# Charger_Main_Power.net
KiCad netlist of a schematic drawn in Altium Designer
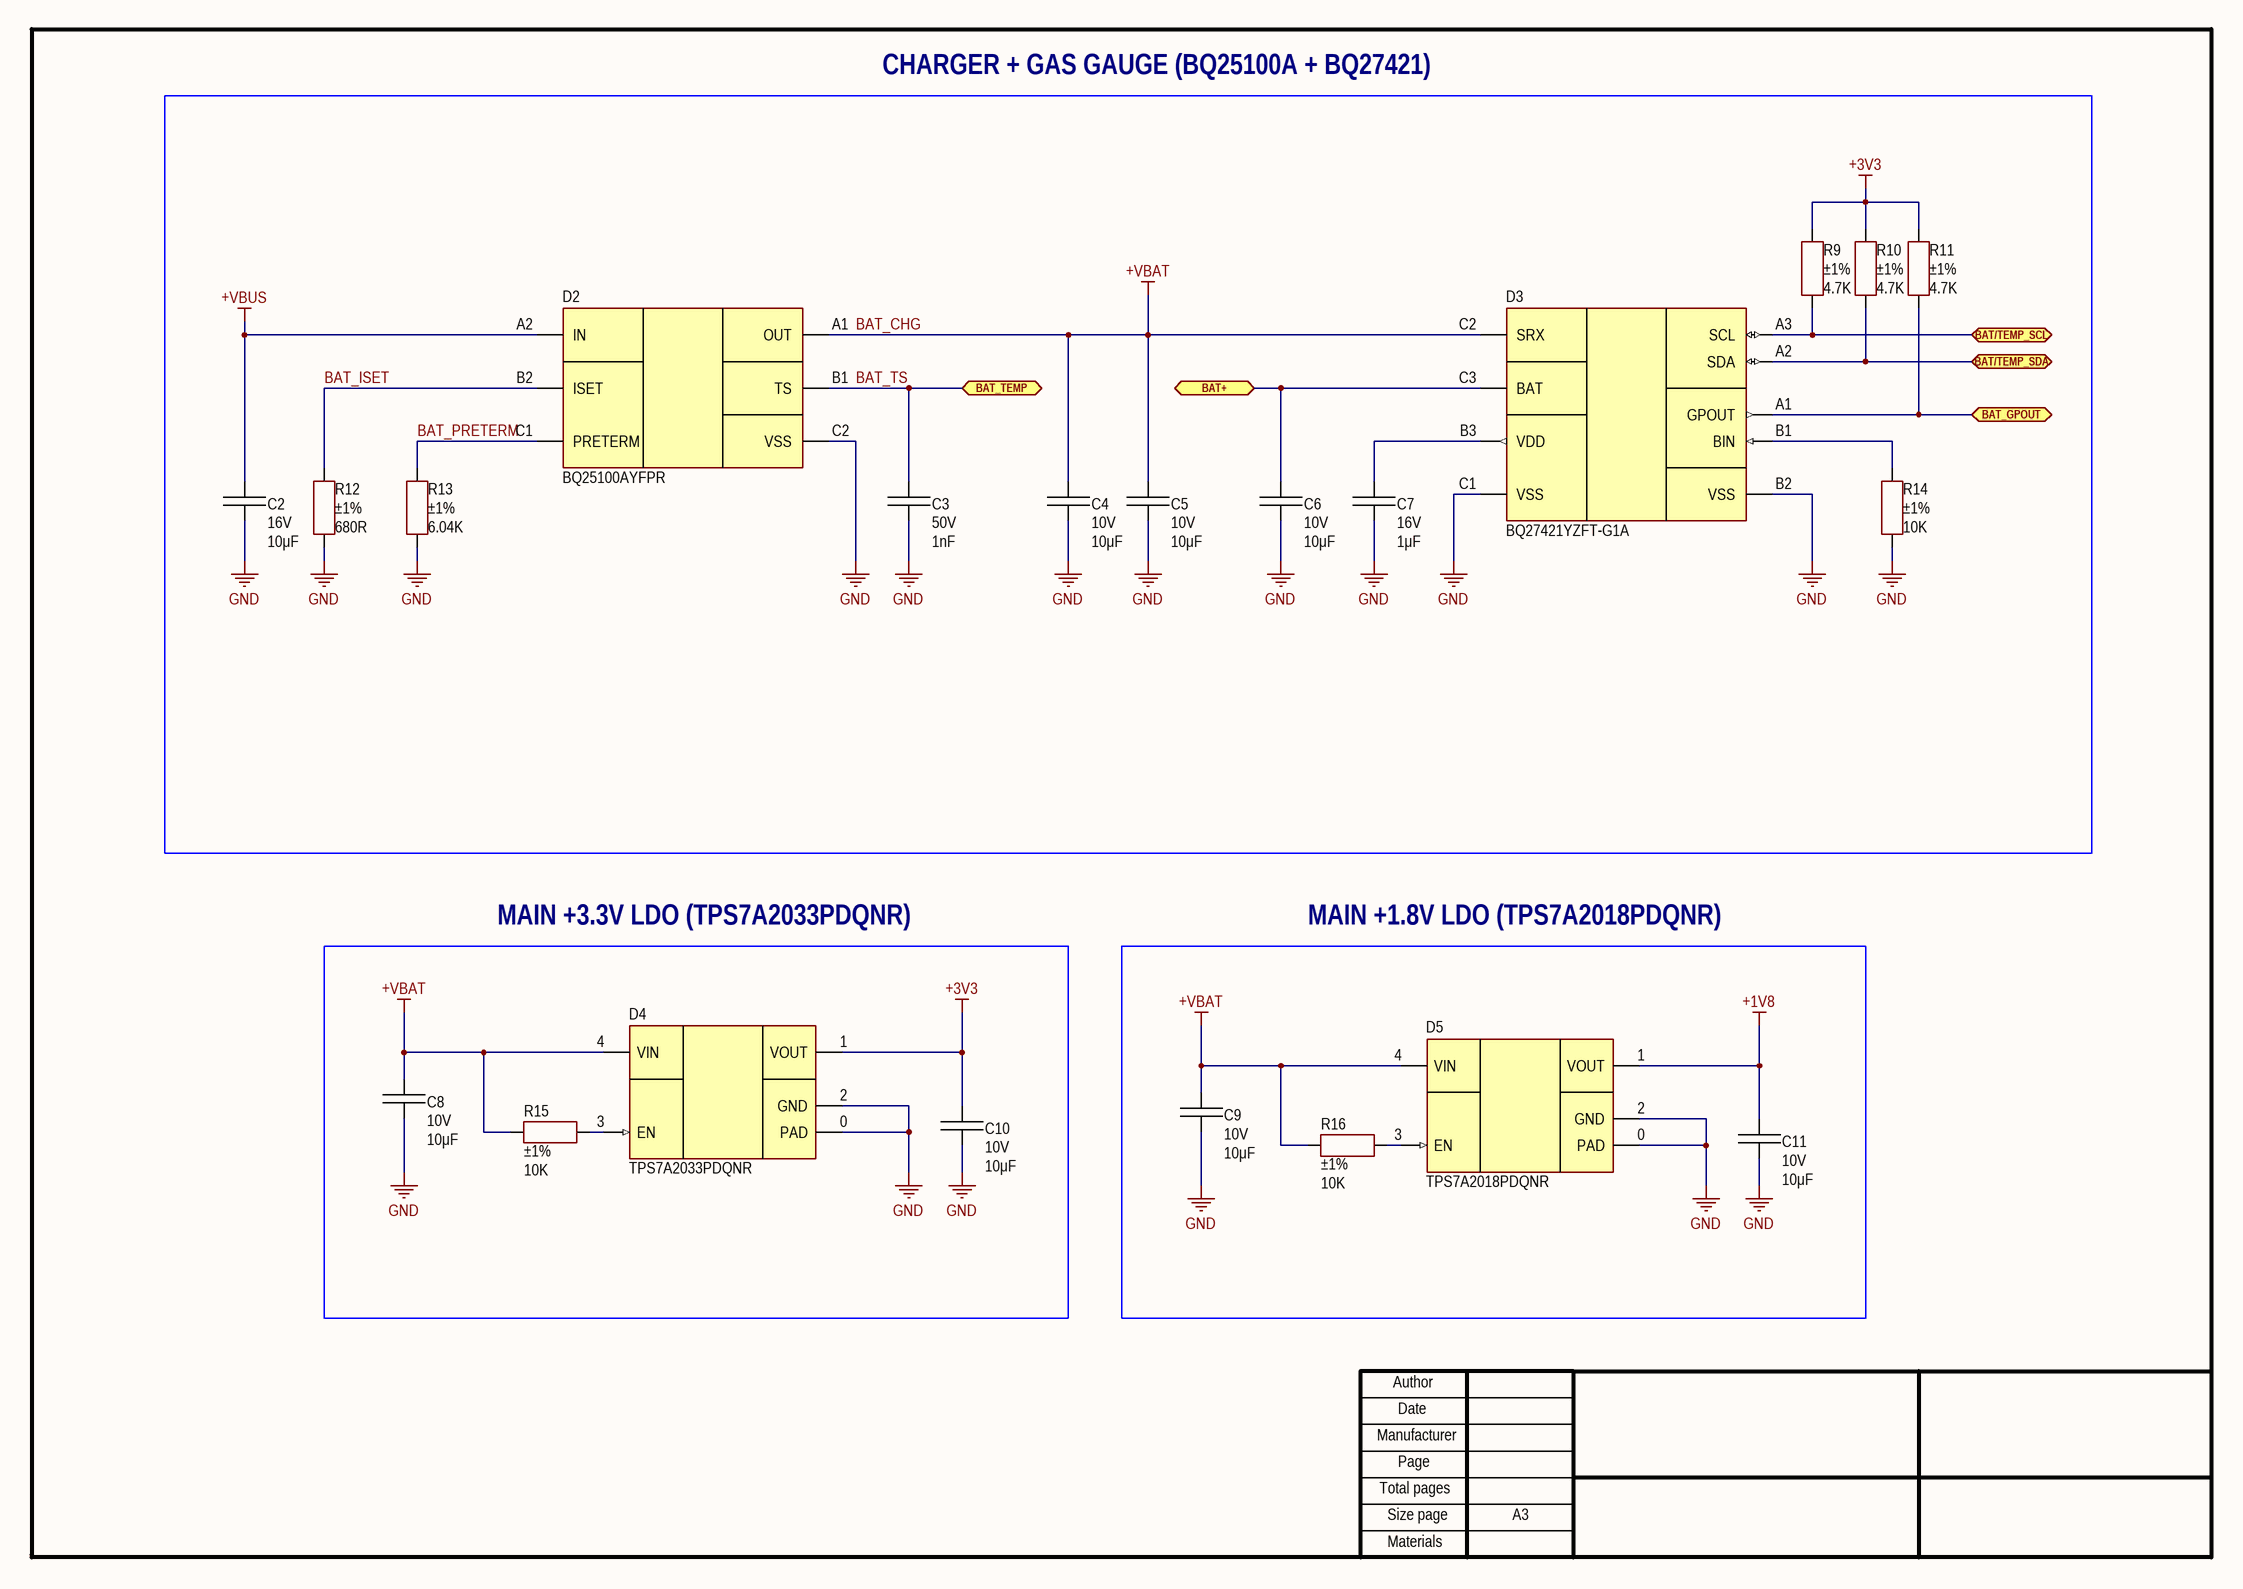
[diagram p0: Charger+Main_Power — копия.SchDoc]

(export (version "E")
  (design (tool "Eeschema 10.0.6"))
  (components
    (comp (ref "C2")
      (value "10μF")
      (footprint "CAP: 0805_NO_SILK")
      (description "10 µF ±20% 16V Ceramic Capacitor X7R 0805 (2012 Metric)")
      (fields
        (field (name "MANUFACTURER") "Yageo")
        (field (name "PARTNUMBER") "CC0805MKX7R7BB106")
        (field (name "VOLTAGE") "16V")
      )
      (libsource (lib "capacitor") (part "Ceramic_0805"))
    )
    (comp (ref "C3")
      (value "1nF")
      (footprint "CAP: 0805")
      (description "1000 pF ±5% 50V Ceramic Capacitor C0G, NP0 0805 (2012 Metric)")
      (fields
        (field (name "MANUFACTURER") "Yageo")
        (field (name "PARTNUMBER") "CC0805JRNPO9BN102")
        (field (name "VOLTAGE") "50V")
      )
      (libsource (lib "capacitor") (part "Ceramic_0805"))
    )
    (comp (ref "C4")
      (value "10μF")
      (footprint "CAP: 0805")
      (description "10 µF ±10% 10V Ceramic Capacitor X7R 0805 (2012 Metric)")
      (fields
        (field (name "MANUFACTURER") "Yageo")
        (field (name "PARTNUMBER") "CC0805KFX7R6BB106")
        (field (name "VOLTAGE") "10V")
      )
      (libsource (lib "capacitor") (part "Ceramic_0805"))
    )
    (comp (ref "C5")
      (value "10μF")
      (footprint "CAP: 0805")
      (description "10 µF ±10% 10V Ceramic Capacitor X7R 0805 (2012 Metric)")
      (fields
        (field (name "MANUFACTURER") "Yageo")
        (field (name "PARTNUMBER") "CC0805KFX7R6BB106")
        (field (name "VOLTAGE") "10V")
      )
      (libsource (lib "capacitor") (part "Ceramic_0805"))
    )
    (comp (ref "C6")
      (value "10μF")
      (footprint "CAP: 0805")
      (description "10 µF ±10% 10V Ceramic Capacitor X7R 0805 (2012 Metric)")
      (fields
        (field (name "MANUFACTURER") "Yageo")
        (field (name "PARTNUMBER") "CC0805KFX7R6BB106")
        (field (name "VOLTAGE") "10V")
      )
      (libsource (lib "capacitor") (part "Ceramic_0805"))
    )
    (comp (ref "C7")
      (value "1μF")
      (footprint "CAP: 0805")
      (description "1 µF ±10% 16V Ceramic Capacitor X7R 0805 (2012 Metric)")
      (fields
        (field (name "MANUFACTURER") "Yageo")
        (field (name "PARTNUMBER") "CC0805KKX7R7BB105")
        (field (name "VOLTAGE") "16V")
      )
      (libsource (lib "capacitor") (part "Ceramic_0805"))
    )
    (comp (ref "C8")
      (value "10μF")
      (footprint "CAP: 0805")
      (description "10 µF ±10% 10V Ceramic Capacitor X7R 0805 (2012 Metric)")
      (fields
        (field (name "MANUFACTURER") "Yageo")
        (field (name "PARTNUMBER") "CC0805KFX7R6BB106")
        (field (name "VOLTAGE") "10V")
      )
      (libsource (lib "capacitor") (part "Ceramic_0805"))
    )
    (comp (ref "C9")
      (value "10μF")
      (footprint "CAP: 0805")
      (description "10 µF ±10% 10V Ceramic Capacitor X7R 0805 (2012 Metric)")
      (fields
        (field (name "MANUFACTURER") "Yageo")
        (field (name "PARTNUMBER") "CC0805KFX7R6BB106")
        (field (name "VOLTAGE") "10V")
      )
      (libsource (lib "capacitor") (part "Ceramic_0805"))
    )
    (comp (ref "C10")
      (value "10μF")
      (footprint "CAP: 0805")
      (description "10 µF ±10% 10V Ceramic Capacitor X7R 0805 (2012 Metric)")
      (fields
        (field (name "MANUFACTURER") "Yageo")
        (field (name "PARTNUMBER") "CC0805KFX7R6BB106")
        (field (name "VOLTAGE") "10V")
      )
      (libsource (lib "capacitor") (part "Ceramic_0805"))
    )
    (comp (ref "C11")
      (value "10μF")
      (footprint "CAP: 0805")
      (description "10 µF ±10% 10V Ceramic Capacitor X7R 0805 (2012 Metric)")
      (fields
        (field (name "MANUFACTURER") "Yageo")
        (field (name "PARTNUMBER") "CC0805KFX7R6BB106")
        (field (name "VOLTAGE") "10V")
      )
      (libsource (lib "capacitor") (part "Ceramic_0805"))
    )
    (comp (ref "D2")
      (value "~")
      (footprint "IC: BQ25100")
      (description "PMIC")
      (fields
        (field (name "MANUFACTURER") "Texas Instruments")
        (field (name "VALUEMANUFACTURERPARTNUMBER") "PMIC, Li-Ion/Li-Po, 4.45...6.45V, -40...+85°C, 10-WSON")
        (field (name "PARTNUMBER") "BQ25100AYFPR")
      )
      (libsource (lib "MyLib") (part "BQ25100AYFPR"))
    )
    (comp (ref "D3")
      (value "~")
      (footprint "IC: 9-DSBGA")
      (description "Gas gauge")
      (fields
        (field (name "MANUFACTURER") "Texas Instruments")
        (field (name "VALUEMANUFACTURERPARTNUMBER") "Gas gauge, Li-Ion, 2.45...4.5V, -40...+85°C, 9-DSBGA")
        (field (name "PARTNUMBER") "BQ27421YZFT-G1A")
      )
      (libsource (lib "MyLib") (part "BQ25100AYFPR_1"))
    )
    (comp (ref "D4")
      (value "~")
      (footprint "IC: 4-X2SON")
      (description "Linear voltage regulator")
      (fields
        (field (name "MANUFACTURER") "Texas Instruments")
        (field (name "VALUEMANUFACTURERPARTNUMBER") "Linear voltage regulator, input 3.44...6V, 2V, 3.3V, 0.3A, -40...+125°C, 4-X2SON")
        (field (name "PARTNUMBER") "TPS7A2033PDQNR")
      )
      (libsource (lib "MyLib") (part "TPS7A2033"))
    )
    (comp (ref "D5")
      (value "~")
      (footprint "IC: 4-X2SON")
      (description "Linear voltage regulator")
      (fields
        (field (name "MANUFACTURER") "Texas Instruments")
        (field (name "VALUEMANUFACTURERPARTNUMBER") "Linear voltage regulator, input 2...6V, 2V, 1.8V, 0.3A, -40...+125°C, 4-X2SON")
        (field (name "PARTNUMBER") "TPS7A2018PDQNR")
      )
      (libsource (lib "MyLib") (part "TPS7A2033"))
    )
    (comp (ref "R9")
      (value "4.7K")
      (footprint "RES: 0805")
      (description "4.7 kOhms ±5% 0.125W, 1/8W Chip Resistor 0805 (2012 Metric) Moisture Resistant Thick Film")
      (fields
        (field (name "MANUFACTURER") "Yageo")
        (field (name "PARTNUMBER") "RC0805JR-074K7L")
        (field (name "TOLERANCE") "±1%")
      )
      (libsource (lib "resistor") (part "Resistor_0805"))
    )
    (comp (ref "R10")
      (value "4.7K")
      (footprint "RES: 0805")
      (description "4.7 kOhms ±5% 0.125W, 1/8W Chip Resistor 0805 (2012 Metric) Moisture Resistant Thick Film")
      (fields
        (field (name "MANUFACTURER") "Yageo")
        (field (name "PARTNUMBER") "RC0805JR-074K7L")
        (field (name "TOLERANCE") "±1%")
      )
      (libsource (lib "resistor") (part "Resistor_0805"))
    )
    (comp (ref "R11")
      (value "4.7K")
      (footprint "RES: 0805")
      (description "4.7 kOhms ±5% 0.125W, 1/8W Chip Resistor 0805 (2012 Metric) Moisture Resistant Thick Film")
      (fields
        (field (name "MANUFACTURER") "Yageo")
        (field (name "PARTNUMBER") "RC0805JR-074K7L")
        (field (name "TOLERANCE") "±1%")
      )
      (libsource (lib "resistor") (part "Resistor_0805"))
    )
    (comp (ref "R12")
      (value "680R")
      (footprint "RES: 0805")
      (description "680 Ohms ±1% 0.125W, 1/8W Chip Resistor 0805 (2012 Metric) Moisture Resistant Thick Film")
      (fields
        (field (name "MANUFACTURER") "Yageo")
        (field (name "PARTNUMBER") "RC0805FR-07680RL")
        (field (name "TOLERANCE") "±1%")
      )
      (libsource (lib "resistor") (part "Resistor_0805"))
    )
    (comp (ref "R13")
      (value "6.04K")
      (footprint "RES: 0805")
      (description "6.04 kOhms ±1% 0.125W, 1/8W Chip Resistor 0805 (2012 Metric) Moisture Resistant Thick Film")
      (fields
        (field (name "MANUFACTURER") "Yageo")
        (field (name "PARTNUMBER") "RC0805FR-076K04L")
        (field (name "TOLERANCE") "±1%")
      )
      (libsource (lib "resistor") (part "Resistor_0805"))
    )
    (comp (ref "R14")
      (value "10K")
      (footprint "RES: 0805")
      (description "10 kOhms ±1% 0.125W, 1/8W Chip Resistor 0805 (2012 Metric) Moisture Resistant Thick Film")
      (fields
        (field (name "MANUFACTURER") "Yageo")
        (field (name "PARTNUMBER") "RC0805FR-0710KL")
        (field (name "TOLERANCE") "±1%")
      )
      (libsource (lib "resistor") (part "Resistor_0805"))
    )
    (comp (ref "R15")
      (value "10K")
      (footprint "RES: 0805")
      (description "10 kOhms ±1% 0.125W, 1/8W Chip Resistor 0805 (2012 Metric) Moisture Resistant Thick Film")
      (fields
        (field (name "MANUFACTURER") "Yageo")
        (field (name "PARTNUMBER") "RC0805FR-0710KL")
        (field (name "TOLERANCE") "±1%")
      )
      (libsource (lib "") (part "Resistor_0805_1"))
    )
    (comp (ref "R16")
      (value "10K")
      (footprint "RES: 0805")
      (description "10 kOhms ±1% 0.125W, 1/8W Chip Resistor 0805 (2012 Metric) Moisture Resistant Thick Film")
      (fields
        (field (name "MANUFACTURER") "Yageo")
        (field (name "PARTNUMBER") "RC0805FR-0710KL")
        (field (name "TOLERANCE") "±1%")
      )
      (libsource (lib "") (part "Resistor_0805_1"))
    )
  )
  (nets
    (net (code "1") (name "+1V8") (class "Default")
      (node (ref "C11") (pin "2") (pinfunction "2_2") (pintype "passive"))
      (node (ref "D5") (pin "1") (pinfunction "VOUT_1") (pintype "power_in"))
    )
    (net (code "2") (name "+3V3") (class "Default")
      (node (ref "C10") (pin "2") (pinfunction "2_2") (pintype "passive"))
      (node (ref "D4") (pin "1") (pinfunction "VOUT_1") (pintype "power_in"))
      (node (ref "R10") (pin "1") (pinfunction "1_1") (pintype "passive"))
      (node (ref "R11") (pin "1") (pinfunction "1_1") (pintype "passive"))
      (node (ref "R9") (pin "1") (pinfunction "1_1") (pintype "passive"))
    )
    (net (code "3") (name "+VBAT") (class "Default")
      (node (ref "C4") (pin "2") (pinfunction "2_2") (pintype "passive"))
      (node (ref "C5") (pin "2") (pinfunction "2_2") (pintype "passive"))
      (node (ref "C8") (pin "2") (pinfunction "2_2") (pintype "passive"))
      (node (ref "C9") (pin "2") (pinfunction "2_2") (pintype "passive"))
      (node (ref "D2") (pin "A1") (pinfunction "OUT_A1") (pintype "passive"))
      (node (ref "D3") (pin "C2") (pinfunction "SRX_C2") (pintype "power_in"))
      (node (ref "D4") (pin "4") (pinfunction "VIN_4") (pintype "power_in"))
      (node (ref "D5") (pin "4") (pinfunction "VIN_4") (pintype "power_in"))
      (node (ref "R15") (pin "2") (pinfunction "2_2") (pintype "passive"))
      (node (ref "R16") (pin "2") (pinfunction "2_2") (pintype "passive"))
    )
    (net (code "4") (name "+VBUS") (class "Default")
      (node (ref "C2") (pin "2") (pinfunction "2_2") (pintype "passive"))
      (node (ref "D2") (pin "A2") (pinfunction "IN_A2") (pintype "passive"))
    )
    (net (code "5") (name "/BAT+") (class "Default")
      (node (ref "C6") (pin "2") (pinfunction "2_2") (pintype "passive"))
      (node (ref "D3") (pin "C3") (pinfunction "BAT_C3") (pintype "power_in"))
    )
    (net (code "6") (name "/BAT_GPOUT") (class "Default")
      (node (ref "D3") (pin "A1") (pinfunction "GPOUT_A1") (pintype "output"))
      (node (ref "R11") (pin "2") (pinfunction "2_2") (pintype "passive"))
    )
    (net (code "7") (name "/BAT_ISET") (class "Default")
      (node (ref "D2") (pin "B2") (pinfunction "ISET_B2") (pintype "passive"))
      (node (ref "R12") (pin "1") (pinfunction "1_1") (pintype "passive"))
    )
    (net (code "8") (name "/BAT_PRETERM") (class "Default")
      (node (ref "D2") (pin "C1") (pinfunction "PRETERM_C1") (pintype "passive"))
      (node (ref "R13") (pin "1") (pinfunction "1_1") (pintype "passive"))
    )
    (net (code "9") (name "/BAT_TS") (class "Default")
      (node (ref "C3") (pin "2") (pinfunction "2_2") (pintype "passive"))
      (node (ref "D2") (pin "B1") (pinfunction "TS_B1") (pintype "passive"))
    )
    (net (code "10") (name "/BAT{slash}TEMP_SCL") (class "Default")
      (node (ref "D3") (pin "A3") (pinfunction "SCL_A3") (pintype "bidirectional"))
      (node (ref "R9") (pin "2") (pinfunction "2_2") (pintype "passive"))
    )
    (net (code "11") (name "/BAT{slash}TEMP_SDA") (class "Default")
      (node (ref "D3") (pin "A2") (pinfunction "SDA_A2") (pintype "bidirectional"))
      (node (ref "R10") (pin "2") (pinfunction "2_2") (pintype "passive"))
    )
    (net (code "12") (name "GND") (class "Default")
      (node (ref "C10") (pin "1") (pinfunction "1_1") (pintype "passive"))
      (node (ref "C11") (pin "1") (pinfunction "1_1") (pintype "passive"))
      (node (ref "C2") (pin "1") (pinfunction "1_1") (pintype "passive"))
      (node (ref "C3") (pin "1") (pinfunction "1_1") (pintype "passive"))
      (node (ref "C4") (pin "1") (pinfunction "1_1") (pintype "passive"))
      (node (ref "C5") (pin "1") (pinfunction "1_1") (pintype "passive"))
      (node (ref "C6") (pin "1") (pinfunction "1_1") (pintype "passive"))
      (node (ref "C7") (pin "1") (pinfunction "1_1") (pintype "passive"))
      (node (ref "C8") (pin "1") (pinfunction "1_1") (pintype "passive"))
      (node (ref "C9") (pin "1") (pinfunction "1_1") (pintype "passive"))
      (node (ref "D2") (pin "C2") (pinfunction "VSS_C2") (pintype "passive"))
      (node (ref "D3") (pin "B2") (pinfunction "VSS_B2") (pintype "power_in"))
      (node (ref "D3") (pin "C1") (pinfunction "VSS_C1") (pintype "power_in"))
      (node (ref "D4") (pin "0") (pinfunction "PAD_0") (pintype "power_in"))
      (node (ref "D4") (pin "2") (pinfunction "GND_2") (pintype "power_in"))
      (node (ref "D5") (pin "0") (pinfunction "PAD_0") (pintype "power_in"))
      (node (ref "D5") (pin "2") (pinfunction "GND_2") (pintype "power_in"))
      (node (ref "R12") (pin "2") (pinfunction "2_2") (pintype "passive"))
      (node (ref "R13") (pin "2") (pinfunction "2_2") (pintype "passive"))
      (node (ref "R14") (pin "2") (pinfunction "2_2") (pintype "passive"))
    )
    (net (code "13") (name "Net-(D3-BIN)") (class "Default")
      (node (ref "D3") (pin "B1") (pinfunction "BIN_B1") (pintype "input"))
      (node (ref "R14") (pin "1") (pinfunction "1_1") (pintype "passive"))
    )
    (net (code "14") (name "Net-(D3-VDD)") (class "Default")
      (node (ref "C7") (pin "2") (pinfunction "2_2") (pintype "passive"))
      (node (ref "D3") (pin "B3") (pinfunction "VDD_B3") (pintype "output"))
    )
    (net (code "15") (name "Net-(D4-EN)") (class "Default")
      (node (ref "D4") (pin "3") (pinfunction "EN_3") (pintype "input"))
      (node (ref "R15") (pin "1") (pinfunction "1_1") (pintype "passive"))
    )
    (net (code "16") (name "Net-(D5-EN)") (class "Default")
      (node (ref "D5") (pin "3") (pinfunction "EN_3") (pintype "input"))
      (node (ref "R16") (pin "1") (pinfunction "1_1") (pintype "passive"))
    )
  )
)
